# evpr_programmer.net
KiCad netlist of a schematic drawn in EAGLE
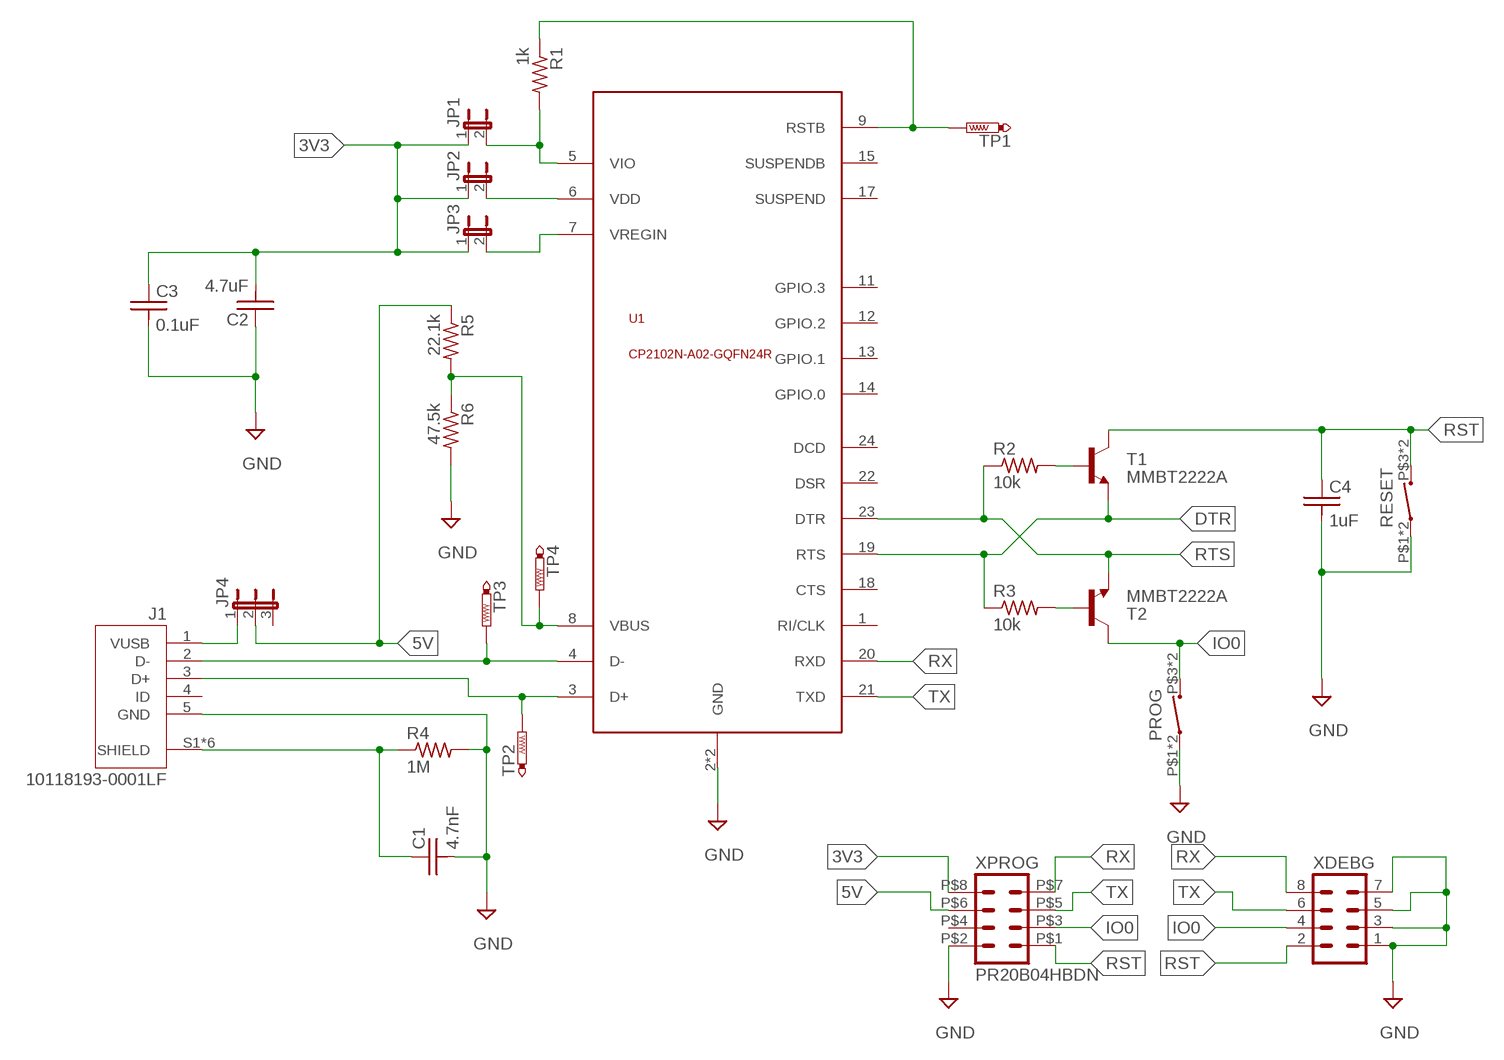
[diagram p0: schematic, sheet 1]

(export (version "E")
  (design (tool "Eeschema 10.0.6"))
  (components
    (comp (ref "C1")
      (value "4.7nF")
      (footprint "eagle-import:C0603")
      (libsource (lib "eagle-import") (part "C0603"))
    )
    (comp (ref "C2")
      (value "4.7uF")
      (footprint "eagle-import:C0603")
      (libsource (lib "eagle-import") (part "C0603"))
    )
    (comp (ref "C3")
      (value "0.1uF")
      (footprint "eagle-import:C0603")
      (libsource (lib "eagle-import") (part "C0603"))
    )
    (comp (ref "C4")
      (value "1uF")
      (footprint "eagle-import:C0603")
      (libsource (lib "eagle-import") (part "C0603"))
    )
    (comp (ref "J1")
      (value "10118193-0001LF")
      (footprint "eagle-import:FCI_10118193-0001LF")
      (fields (field (name "DIGI-KEY_PART_NUMBER") "609-4616-1-ND") (field (name "MF") "Amphenol ICC"))
      (libsource (lib "eagle-import") (part "10118193-0001LF"))
    )
    (comp (ref "JP1")
      (value "JP1E")
      (footprint "eagle-import:JP1")
      (libsource (lib "eagle-import") (part "JP1E"))
    )
    (comp (ref "JP2")
      (value "JP1E")
      (footprint "eagle-import:JP1")
      (libsource (lib "eagle-import") (part "JP1E"))
    )
    (comp (ref "JP3")
      (value "JP1E")
      (footprint "eagle-import:JP1")
      (libsource (lib "eagle-import") (part "JP1E"))
    )
    (comp (ref "JP4")
      (value "JP2E")
      (footprint "eagle-import:JP2")
      (libsource (lib "eagle-import") (part "JP2E"))
    )
    (comp (ref "PROG")
      (value "MOMENTARY_SWITCH")
      (footprint "eagle-import:PTS645")
      (libsource (lib "eagle-import") (part "MOMENTARY_SWITCH"))
    )
    (comp (ref "R1")
      (value "1k")
      (footprint "eagle-import:R0603")
      (libsource (lib "eagle-import") (part "R0603"))
    )
    (comp (ref "R2")
      (value "10k")
      (footprint "eagle-import:R0603")
      (libsource (lib "eagle-import") (part "R0603"))
    )
    (comp (ref "R3")
      (value "10k")
      (footprint "eagle-import:R0603")
      (libsource (lib "eagle-import") (part "R0603"))
    )
    (comp (ref "R4")
      (value "1M")
      (footprint "eagle-import:R0603")
      (libsource (lib "eagle-import") (part "R0603"))
    )
    (comp (ref "R5")
      (value "22.1k")
      (footprint "eagle-import:R0603")
      (libsource (lib "eagle-import") (part "R0603"))
    )
    (comp (ref "R6")
      (value "47.5k")
      (footprint "eagle-import:R0603")
      (libsource (lib "eagle-import") (part "R0603"))
    )
    (comp (ref "RESET")
      (value "MOMENTARY_SWITCH")
      (footprint "eagle-import:PTS645")
      (libsource (lib "eagle-import") (part "MOMENTARY_SWITCH"))
    )
    (comp (ref "T1")
      (value "MMBT2222A")
      (footprint "eagle-import:SOT23-BEC")
      (libsource (lib "eagle-import") (part "-NPN-SOT23-BECMMBT2222ALT1"))
    )
    (comp (ref "T2")
      (value "MMBT2222A")
      (footprint "eagle-import:SOT23-BEC")
      (libsource (lib "eagle-import") (part "-NPN-SOT23-BECMMBT2222ALT1"))
    )
    (comp (ref "TP1")
      (value "PTR1TP10R")
      (footprint "eagle-import:TP10R")
      (libsource (lib "eagle-import") (part "PTR1TP10R"))
    )
    (comp (ref "TP2")
      (value "PTR1TP10R")
      (footprint "eagle-import:TP10R")
      (libsource (lib "eagle-import") (part "PTR1TP10R"))
    )
    (comp (ref "TP3")
      (value "PTR1TP10R")
      (footprint "eagle-import:TP10R")
      (libsource (lib "eagle-import") (part "PTR1TP10R"))
    )
    (comp (ref "TP4")
      (value "PTR1TP10R")
      (footprint "eagle-import:TP10R")
      (libsource (lib "eagle-import") (part "PTR1TP10R"))
    )
    (comp (ref "U1")
      (value "CP2102N-A02-GQFN24R")
      (footprint "eagle-import:QFN24-4X4")
      (libsource (lib "eagle-import") (part "CP2102N-A02-GQFN24R"))
    )
    (comp (ref "XDEBG")
      (value "MA04-2")
      (footprint "eagle-import:MA04-2")
      (libsource (lib "eagle-import") (part "MA04-2"))
    )
    (comp (ref "XPROG")
      (value "PR20B04HBDN")
      (footprint "eagle-import:PR20B04HBDN")
      (libsource (lib "eagle-import") (part "PR20B04HBDN"))
    )
  )
  (nets
    (net (code "1") (name "3V3") (class "Default")
      (node (ref "C2") (pin "2") (pinfunction "2_2") (pintype "passive"))
      (node (ref "C3") (pin "1") (pinfunction "1_1") (pintype "passive"))
      (node (ref "JP1") (pin "1") (pinfunction "1_1") (pintype "passive"))
      (node (ref "JP2") (pin "1") (pinfunction "1_1") (pintype "passive"))
      (node (ref "JP3") (pin "1") (pinfunction "1_1") (pintype "passive"))
      (node (ref "XPROG") (pin "P$8") (pinfunction "8_P$8") (pintype "passive"))
    )
    (net (code "2") (name "5V") (class "Default")
      (node (ref "JP4") (pin "2") (pinfunction "2_2") (pintype "passive"))
      (node (ref "R5") (pin "1") (pinfunction "1_1") (pintype "passive"))
      (node (ref "XPROG") (pin "P$6") (pinfunction "6_P$6") (pintype "passive"))
    )
    (net (code "3") (name "DTR") (class "Default")
      (node (ref "R3") (pin "1") (pinfunction "1_1") (pintype "passive"))
      (node (ref "T1") (pin "E") (pinfunction "E_E") (pintype "passive"))
      (node (ref "U1") (pin "19") (pinfunction "RTS_19") (pintype "bidirectional"))
    )
    (net (code "4") (name "GND") (class "Default")
      (node (ref "C1") (pin "2") (pinfunction "2_2") (pintype "passive"))
      (node (ref "C2") (pin "1") (pinfunction "1_1") (pintype "passive"))
      (node (ref "C3") (pin "2") (pinfunction "2_2") (pintype "passive"))
      (node (ref "C4") (pin "2") (pinfunction "2_2") (pintype "passive"))
      (node (ref "J1") (pin "5") (pinfunction "GND_5") (pintype "passive"))
      (node (ref "PROG") (pin "P$1") (pinfunction "1_P$1") (pintype "passive"))
      (node (ref "PROG") (pin "P$2") (pinfunction "1_P$2") (pintype "passive"))
      (node (ref "R4") (pin "2") (pinfunction "2_2") (pintype "passive"))
      (node (ref "R6") (pin "2") (pinfunction "2_2") (pintype "passive"))
      (node (ref "RESET") (pin "P$1") (pinfunction "1_P$1") (pintype "passive"))
      (node (ref "RESET") (pin "P$2") (pinfunction "1_P$2") (pintype "passive"))
      (node (ref "U1") (pin "2") (pinfunction "GND_2") (pintype "bidirectional"))
      (node (ref "U1") (pin "EXP") (pinfunction "GND_EXP") (pintype "bidirectional"))
      (node (ref "XDEBG") (pin "1") (pinfunction "1_1") (pintype "passive"))
      (node (ref "XDEBG") (pin "3") (pinfunction "3_3") (pintype "passive"))
      (node (ref "XDEBG") (pin "5") (pinfunction "5_5") (pintype "passive"))
      (node (ref "XDEBG") (pin "7") (pinfunction "7_7") (pintype "passive"))
      (node (ref "XPROG") (pin "P$2") (pinfunction "2_P$2") (pintype "passive"))
    )
    (net (code "5") (name "IO0") (class "Default")
      (node (ref "PROG") (pin "P$3") (pinfunction "2_P$3") (pintype "passive"))
      (node (ref "PROG") (pin "P$4") (pinfunction "2_P$4") (pintype "passive"))
      (node (ref "T2") (pin "C") (pinfunction "C_C") (pintype "passive"))
      (node (ref "XDEBG") (pin "4") (pinfunction "4_4") (pintype "passive"))
      (node (ref "XPROG") (pin "P$3") (pinfunction "3_P$3") (pintype "passive"))
    )
    (net (code "6") (name "Net-(C1-Pad1)") (class "Default")
      (node (ref "C1") (pin "1") (pinfunction "1_1") (pintype "passive"))
      (node (ref "J1") (pin "S1") (pinfunction "SHIELD_S1") (pintype "passive"))
      (node (ref "J1") (pin "S2") (pinfunction "SHIELD_S2") (pintype "passive"))
      (node (ref "J1") (pin "S3") (pinfunction "SHIELD_S3") (pintype "passive"))
      (node (ref "J1") (pin "S4") (pinfunction "SHIELD_S4") (pintype "passive"))
      (node (ref "J1") (pin "S5") (pinfunction "SHIELD_S5") (pintype "passive"))
      (node (ref "J1") (pin "S6") (pinfunction "SHIELD_S6") (pintype "passive"))
      (node (ref "R4") (pin "1") (pinfunction "1_1") (pintype "passive"))
    )
    (net (code "7") (name "Net-(J1-D+)") (class "Default")
      (node (ref "J1") (pin "3") (pinfunction "D+_3") (pintype "passive"))
      (node (ref "TP2") (pin "TP") (pinfunction "TP_TP") (pintype "input"))
      (node (ref "U1") (pin "3") (pinfunction "D+_3") (pintype "bidirectional"))
    )
    (net (code "8") (name "Net-(J1-D-)") (class "Default")
      (node (ref "J1") (pin "2") (pinfunction "D-_2") (pintype "passive"))
      (node (ref "TP3") (pin "TP") (pinfunction "TP_TP") (pintype "input"))
      (node (ref "U1") (pin "4") (pinfunction "D-_4") (pintype "bidirectional"))
    )
    (net (code "9") (name "Net-(J1-VUSB)") (class "Default")
      (node (ref "J1") (pin "1") (pinfunction "VUSB_1") (pintype "passive"))
      (node (ref "JP4") (pin "1") (pinfunction "1_1") (pintype "passive"))
    )
    (net (code "10") (name "Net-(R2-Pad2)") (class "Default")
      (node (ref "R2") (pin "2") (pinfunction "2_2") (pintype "passive"))
      (node (ref "T1") (pin "B") (pinfunction "B_B") (pintype "passive"))
    )
    (net (code "11") (name "Net-(R3-Pad2)") (class "Default")
      (node (ref "R3") (pin "2") (pinfunction "2_2") (pintype "passive"))
      (node (ref "T2") (pin "B") (pinfunction "B_B") (pintype "passive"))
    )
    (net (code "12") (name "Net-(U1-RSTB)") (class "Default")
      (node (ref "R1") (pin "1") (pinfunction "1_1") (pintype "passive"))
      (node (ref "TP1") (pin "TP") (pinfunction "TP_TP") (pintype "input"))
      (node (ref "U1") (pin "9") (pinfunction "RSTB_9") (pintype "bidirectional"))
    )
    (net (code "13") (name "Net-(U1-VBUS)") (class "Default")
      (node (ref "R5") (pin "2") (pinfunction "2_2") (pintype "passive"))
      (node (ref "R6") (pin "1") (pinfunction "1_1") (pintype "passive"))
      (node (ref "TP4") (pin "TP") (pinfunction "TP_TP") (pintype "input"))
      (node (ref "U1") (pin "8") (pinfunction "VBUS_8") (pintype "bidirectional"))
    )
    (net (code "14") (name "Net-(U1-VDD)") (class "Default")
      (node (ref "JP2") (pin "2") (pinfunction "2_2") (pintype "passive"))
      (node (ref "U1") (pin "6") (pinfunction "VDD_6") (pintype "bidirectional"))
    )
    (net (code "15") (name "Net-(U1-VIO)") (class "Default")
      (node (ref "JP1") (pin "2") (pinfunction "2_2") (pintype "passive"))
      (node (ref "R1") (pin "2") (pinfunction "2_2") (pintype "passive"))
      (node (ref "U1") (pin "5") (pinfunction "VIO_5") (pintype "bidirectional"))
    )
    (net (code "16") (name "Net-(U1-VREGIN)") (class "Default")
      (node (ref "JP3") (pin "2") (pinfunction "2_2") (pintype "passive"))
      (node (ref "U1") (pin "7") (pinfunction "VREGIN_7") (pintype "bidirectional"))
    )
    (net (code "17") (name "RST") (class "Default")
      (node (ref "C4") (pin "1") (pinfunction "1_1") (pintype "passive"))
      (node (ref "RESET") (pin "P$3") (pinfunction "2_P$3") (pintype "passive"))
      (node (ref "RESET") (pin "P$4") (pinfunction "2_P$4") (pintype "passive"))
      (node (ref "T1") (pin "C") (pinfunction "C_C") (pintype "passive"))
      (node (ref "XDEBG") (pin "2") (pinfunction "2_2") (pintype "passive"))
      (node (ref "XPROG") (pin "P$1") (pinfunction "1_P$1") (pintype "passive"))
    )
    (net (code "18") (name "RTS") (class "Default")
      (node (ref "R2") (pin "1") (pinfunction "1_1") (pintype "passive"))
      (node (ref "T2") (pin "E") (pinfunction "E_E") (pintype "passive"))
      (node (ref "U1") (pin "23") (pinfunction "DTR_23") (pintype "bidirectional"))
    )
    (net (code "19") (name "RX") (class "Default")
      (node (ref "U1") (pin "20") (pinfunction "RXD_20") (pintype "bidirectional"))
      (node (ref "XDEBG") (pin "8") (pinfunction "8_8") (pintype "passive"))
      (node (ref "XPROG") (pin "P$7") (pinfunction "7_P$7") (pintype "passive"))
    )
    (net (code "20") (name "TX") (class "Default")
      (node (ref "U1") (pin "21") (pinfunction "TXD_21") (pintype "bidirectional"))
      (node (ref "XDEBG") (pin "6") (pinfunction "6_6") (pintype "passive"))
      (node (ref "XPROG") (pin "P$5") (pinfunction "5_P$5") (pintype "passive"))
    )
    (net (code "21") (name "unconnected-(J1-ID-Pad4)") (class "Default")
      (node (ref "J1") (pin "4") (pinfunction "ID_4") (pintype "passive"))
    )
    (net (code "22") (name "unconnected-(JP4-Pad3)") (class "Default")
      (node (ref "JP4") (pin "3") (pinfunction "3_3") (pintype "passive"))
    )
    (net (code "23") (name "unconnected-(U1-CTS-Pad18)") (class "Default")
      (node (ref "U1") (pin "18") (pinfunction "CTS_18") (pintype "bidirectional"))
    )
    (net (code "24") (name "unconnected-(U1-DCD-Pad24)") (class "Default")
      (node (ref "U1") (pin "24") (pinfunction "DCD_24") (pintype "bidirectional"))
    )
    (net (code "25") (name "unconnected-(U1-DSR-Pad22)") (class "Default")
      (node (ref "U1") (pin "22") (pinfunction "DSR_22") (pintype "bidirectional"))
    )
    (net (code "26") (name "unconnected-(U1-GPIO.0-Pad14)") (class "Default")
      (node (ref "U1") (pin "14") (pinfunction "GPIO.0_14") (pintype "bidirectional"))
    )
    (net (code "27") (name "unconnected-(U1-GPIO.1-Pad13)") (class "Default")
      (node (ref "U1") (pin "13") (pinfunction "GPIO.1_13") (pintype "bidirectional"))
    )
    (net (code "28") (name "unconnected-(U1-GPIO.2-Pad12)") (class "Default")
      (node (ref "U1") (pin "12") (pinfunction "GPIO.2_12") (pintype "bidirectional"))
    )
    (net (code "29") (name "unconnected-(U1-GPIO.3-Pad11)") (class "Default")
      (node (ref "U1") (pin "11") (pinfunction "GPIO.3_11") (pintype "bidirectional"))
    )
    (net (code "30") (name "unconnected-(U1-RI{slash}CLK-Pad1)") (class "Default")
      (node (ref "U1") (pin "1") (pinfunction "RI/CLK_1") (pintype "bidirectional"))
    )
    (net (code "31") (name "unconnected-(U1-SUSPEND-Pad17)") (class "Default")
      (node (ref "U1") (pin "17") (pinfunction "SUSPEND_17") (pintype "bidirectional"))
    )
    (net (code "32") (name "unconnected-(U1-SUSPENDB-Pad15)") (class "Default")
      (node (ref "U1") (pin "15") (pinfunction "SUSPENDB_15") (pintype "bidirectional"))
    )
    (net (code "33") (name "unconnected-(XPROG-4-PadP$4)") (class "Default")
      (node (ref "XPROG") (pin "P$4") (pinfunction "4_P$4") (pintype "passive"))
    )
  )
)
